# vv_mod_v1.net
KiCad netlist of a schematic drawn in EAGLE
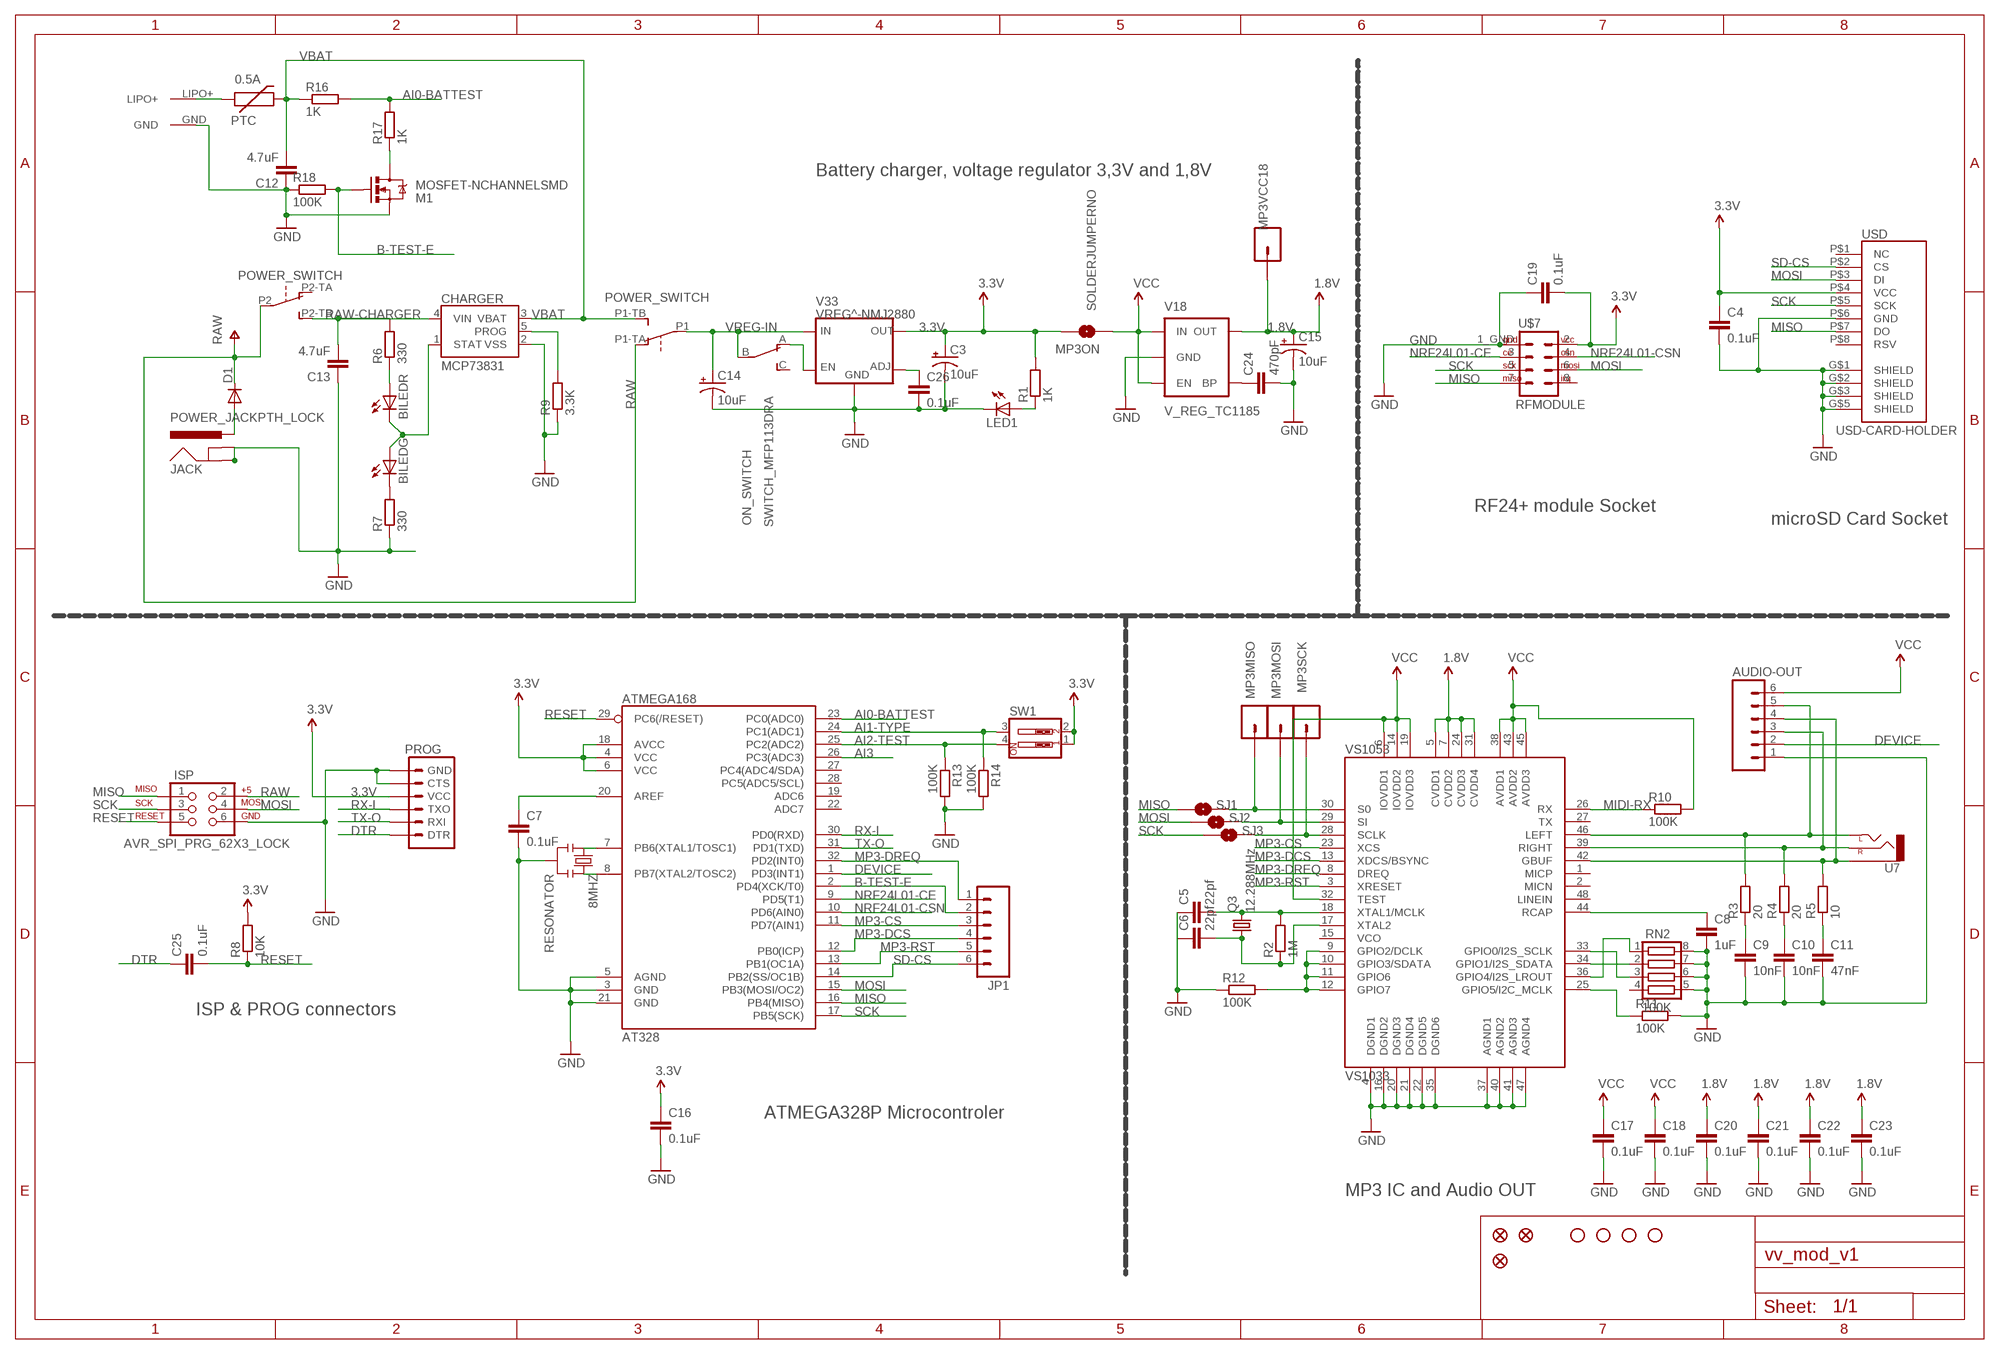
[diagram p0: schematic, sheet 1]

(export (version "E")
  (design (tool "Eeschema 10.0.6"))
  (components
    (comp (ref "0.5A")
      (value "PTC")
      (footprint "eagle-import:PTC-1210")
      (libsource (lib "eagle-import") (part "PTC"))
    )
    (comp (ref "8MHZ")
      (value "RESONATOR")
      (footprint "eagle-import:RESONATOR_7MM")
      (libsource (lib "eagle-import") (part "RESONATOR"))
    )
    (comp (ref "AT328")
      (value "ATMEGA168")
      (footprint "eagle-import:TQFP32-08")
      (libsource (lib "eagle-import") (part "ATMEGA168"))
    )
    (comp (ref "AUDIO-OUT")
      (value "M06LOCK")
      (footprint "eagle-import:1X06_LOCK")
      (libsource (lib "eagle-import") (part "M06LOCK"))
    )
    (comp (ref "BILED")
      (value "BILED")
      (footprint "eagle-import:2XLED")
      (libsource (lib "eagle-import") (part "BILED"))
    )
    (comp (ref "C3")
      (value "10uF")
      (footprint "eagle-import:EIA3216")
      (libsource (lib "eagle-import") (part "CAP_POL1206"))
    )
    (comp (ref "C4")
      (value "0.1uF")
      (footprint "eagle-import:C0805")
      (libsource (lib "eagle-import") (part "C-EUC0805"))
    )
    (comp (ref "C5")
      (value "22pf")
      (footprint "eagle-import:C0603")
      (libsource (lib "eagle-import") (part "C-EUC0603"))
    )
    (comp (ref "C6")
      (value "22pf")
      (footprint "eagle-import:C0603")
      (libsource (lib "eagle-import") (part "C-EUC0603"))
    )
    (comp (ref "C7")
      (value "0.1uF")
      (footprint "eagle-import:C0805")
      (libsource (lib "eagle-import") (part "C-EUC0805"))
    )
    (comp (ref "C8")
      (value "1uF")
      (footprint "eagle-import:C0603")
      (libsource (lib "eagle-import") (part "C-EUC0603"))
    )
    (comp (ref "C9")
      (value "10nF")
      (footprint "eagle-import:C0603")
      (libsource (lib "eagle-import") (part "C-EUC0603"))
    )
    (comp (ref "C10")
      (value "10nF")
      (footprint "eagle-import:C0603")
      (libsource (lib "eagle-import") (part "C-EUC0603"))
    )
    (comp (ref "C11")
      (value "47nF")
      (footprint "eagle-import:C0603")
      (libsource (lib "eagle-import") (part "C-EUC0603"))
    )
    (comp (ref "C12")
      (value "4.7uF")
      (footprint "eagle-import:C0603")
      (libsource (lib "eagle-import") (part "C-EUC0603"))
    )
    (comp (ref "C13")
      (value "4.7uF")
      (footprint "eagle-import:C0603")
      (libsource (lib "eagle-import") (part "C-EUC0603"))
    )
    (comp (ref "C14")
      (value "10uF")
      (footprint "eagle-import:EIA3216")
      (libsource (lib "eagle-import") (part "CAP_POL1206"))
    )
    (comp (ref "C15")
      (value "10uF")
      (footprint "eagle-import:EIA3216")
      (libsource (lib "eagle-import") (part "CAP_POL1206"))
    )
    (comp (ref "C16")
      (value "0.1uF")
      (footprint "eagle-import:C0805")
      (libsource (lib "eagle-import") (part "C-EUC0805"))
    )
    (comp (ref "C17")
      (value "0.1uF")
      (footprint "eagle-import:C0805")
      (libsource (lib "eagle-import") (part "C-EUC0805"))
    )
    (comp (ref "C18")
      (value "0.1uF")
      (footprint "eagle-import:C0805")
      (libsource (lib "eagle-import") (part "C-EUC0805"))
    )
    (comp (ref "C19")
      (value "0.1uF")
      (footprint "eagle-import:C0805")
      (libsource (lib "eagle-import") (part "C-EUC0805"))
    )
    (comp (ref "C20")
      (value "0.1uF")
      (footprint "eagle-import:C0805")
      (libsource (lib "eagle-import") (part "C-EUC0805"))
    )
    (comp (ref "C21")
      (value "0.1uF")
      (footprint "eagle-import:C0805")
      (libsource (lib "eagle-import") (part "C-EUC0805"))
    )
    (comp (ref "C22")
      (value "0.1uF")
      (footprint "eagle-import:C0805")
      (libsource (lib "eagle-import") (part "C-EUC0805"))
    )
    (comp (ref "C23")
      (value "0.1uF")
      (footprint "eagle-import:C0805")
      (libsource (lib "eagle-import") (part "C-EUC0805"))
    )
    (comp (ref "C24")
      (value "470pF")
      (footprint "eagle-import:C0603")
      (libsource (lib "eagle-import") (part "C-EUC0603"))
    )
    (comp (ref "C25")
      (value "0.1uF")
      (footprint "eagle-import:C0805")
      (libsource (lib "eagle-import") (part "C-EUC0805"))
    )
    (comp (ref "C26")
      (value "0.1uF")
      (footprint "eagle-import:C0805")
      (libsource (lib "eagle-import") (part "C-EUC0805"))
    )
    (comp (ref "CHARGER")
      (value "MCP73831")
      (footprint "eagle-import:SOT23-5")
      (libsource (lib "eagle-import") (part "MCP73831"))
    )
    (comp (ref "D1")
      (value "DIODESMA-KIT")
      (footprint "eagle-import:SMA-DIODE-KIT")
      (libsource (lib "eagle-import") (part "DIODESMA-KIT"))
    )
    (comp (ref "ISP")
      (value "AVR_SPI_PRG_62X3_LOCK")
      (footprint "eagle-import:2X3_LOCK")
      (libsource (lib "eagle-import") (part "AVR_SPI_PRG_62X3_LOCK"))
    )
    (comp (ref "JACK")
      (value "POWER_JACKPTH_LOCK")
      (footprint "eagle-import:POWER_JACK_PTH_LOCK")
      (libsource (lib "eagle-import") (part "POWER_JACKPTH_LOCK"))
    )
    (comp (ref "JP1")
      (value "M06SIP")
      (footprint "eagle-import:1X06")
      (libsource (lib "eagle-import") (part "M06SIP"))
    )
    (comp (ref "JP2")
      (value "FIDUCIAL1X2.5")
      (footprint "eagle-import:FIDUCIAL-1X2.5")
      (libsource (lib "eagle-import") (part "FIDUCIAL1X2.5"))
    )
    (comp (ref "JP3")
      (value "FIDUCIAL1X2.5")
      (footprint "eagle-import:FIDUCIAL-1X2.5")
      (libsource (lib "eagle-import") (part "FIDUCIAL1X2.5"))
    )
    (comp (ref "JP4")
      (value "STAND-OFF")
      (footprint "eagle-import:STAND-OFF")
      (libsource (lib "eagle-import") (part "STAND-OFF"))
    )
    (comp (ref "JP5")
      (value "STAND-OFF")
      (footprint "eagle-import:STAND-OFF")
      (libsource (lib "eagle-import") (part "STAND-OFF"))
    )
    (comp (ref "JP6")
      (value "STAND-OFF")
      (footprint "eagle-import:STAND-OFF")
      (libsource (lib "eagle-import") (part "STAND-OFF"))
    )
    (comp (ref "JP7")
      (value "STAND-OFF")
      (footprint "eagle-import:STAND-OFF")
      (libsource (lib "eagle-import") (part "STAND-OFF"))
    )
    (comp (ref "JP8")
      (value "FIDUCIAL1X2.5")
      (footprint "eagle-import:FIDUCIAL-1X2.5")
      (libsource (lib "eagle-import") (part "FIDUCIAL1X2.5"))
    )
    (comp (ref "LED1")
      (value "LED1206")
      (footprint "eagle-import:LED-1206")
      (libsource (lib "eagle-import") (part "LED1206"))
    )
    (comp (ref "M1")
      (value "MOSFET-NCHANNELSMD")
      (footprint "eagle-import:SOT23-3")
      (libsource (lib "eagle-import") (part "MOSFET-NCHANNELSMD"))
    )
    (comp (ref "MP3MISO")
      (value "M01SMD-4.5X1.5")
      (footprint "eagle-import:PAD-1.5X4.5")
      (libsource (lib "eagle-import") (part "M01SMD-4.5X1.5"))
    )
    (comp (ref "MP3MOSI")
      (value "M01SMD-4.5X1.5")
      (footprint "eagle-import:PAD-1.5X4.5")
      (libsource (lib "eagle-import") (part "M01SMD-4.5X1.5"))
    )
    (comp (ref "MP3ON")
      (value "SOLDERJUMPERNO")
      (footprint "eagle-import:SJ_2S-NO")
      (libsource (lib "eagle-import") (part "SOLDERJUMPERNO"))
    )
    (comp (ref "MP3SCK")
      (value "M01SMD-4.5X1.5")
      (footprint "eagle-import:PAD-1.5X4.5")
      (libsource (lib "eagle-import") (part "M01SMD-4.5X1.5"))
    )
    (comp (ref "MP3VCC18")
      (value "M01SMD-4.5X1.5")
      (footprint "eagle-import:PAD-1.5X4.5")
      (libsource (lib "eagle-import") (part "M01SMD-4.5X1.5"))
    )
    (comp (ref "ON_SWITCH")
      (value "SWITCH_MFP113DRA")
      (footprint "eagle-import:SWITCH")
      (libsource (lib "eagle-import") (part "SWITCH_MFP113DRA"))
    )
    (comp (ref "POWER_SWITCH")
      (value "JS202011SCQNPIN")
      (footprint "eagle-import:SWITCHPOWER")
      (libsource (lib "eagle-import") (part "JS202011SCQNPIN"))
    )
    (comp (ref "PROG")
      (value "ARDUINO_SERIAL_PROGRAMLOCK")
      (footprint "eagle-import:1X06_LOCK")
      (libsource (lib "eagle-import") (part "ARDUINO_SERIAL_PROGRAMLOCK"))
    )
    (comp (ref "Q3")
      (value "12.288MHz")
      (footprint "eagle-import:HC49UP")
      (libsource (lib "eagle-import") (part "CRYSTALHC49UP"))
    )
    (comp (ref "R1")
      (value "1K")
      (footprint "eagle-import:R0603")
      (libsource (lib "eagle-import") (part "R-EU_R0603"))
    )
    (comp (ref "R2")
      (value "1M")
      (footprint "eagle-import:R0603")
      (libsource (lib "eagle-import") (part "R-EU_R0603"))
    )
    (comp (ref "R3")
      (value "20")
      (footprint "eagle-import:R0603")
      (libsource (lib "eagle-import") (part "R-EU_R0603"))
    )
    (comp (ref "R4")
      (value "20")
      (footprint "eagle-import:R0603")
      (libsource (lib "eagle-import") (part "R-EU_R0603"))
    )
    (comp (ref "R5")
      (value "10")
      (footprint "eagle-import:R0603")
      (libsource (lib "eagle-import") (part "R-EU_R0603"))
    )
    (comp (ref "R6")
      (value "330")
      (footprint "eagle-import:R0805")
      (libsource (lib "eagle-import") (part "R-EU_R0805"))
    )
    (comp (ref "R7")
      (value "330")
      (footprint "eagle-import:R0805")
      (libsource (lib "eagle-import") (part "R-EU_R0805"))
    )
    (comp (ref "R8")
      (value "10K")
      (footprint "eagle-import:R0603")
      (libsource (lib "eagle-import") (part "R-EU_R0603"))
    )
    (comp (ref "R9")
      (value "3.3K")
      (footprint "eagle-import:R0603")
      (libsource (lib "eagle-import") (part "R-EU_R0603"))
    )
    (comp (ref "R10")
      (value "100K")
      (footprint "eagle-import:R0805")
      (libsource (lib "eagle-import") (part "R-EU_R0805"))
    )
    (comp (ref "R11")
      (value "100K")
      (footprint "eagle-import:R0805")
      (libsource (lib "eagle-import") (part "R-EU_R0805"))
    )
    (comp (ref "R12")
      (value "100K")
      (footprint "eagle-import:R0805")
      (libsource (lib "eagle-import") (part "R-EU_R0805"))
    )
    (comp (ref "R13")
      (value "100K")
      (footprint "eagle-import:R0805")
      (libsource (lib "eagle-import") (part "R-EU_R0805"))
    )
    (comp (ref "R14")
      (value "100K")
      (footprint "eagle-import:R0805")
      (libsource (lib "eagle-import") (part "R-EU_R0805"))
    )
    (comp (ref "R16")
      (value "1K")
      (footprint "eagle-import:R0603")
      (libsource (lib "eagle-import") (part "R-EU_R0603"))
    )
    (comp (ref "R17")
      (value "1K")
      (footprint "eagle-import:R0603")
      (libsource (lib "eagle-import") (part "R-EU_R0603"))
    )
    (comp (ref "R18")
      (value "100K")
      (footprint "eagle-import:R0805")
      (libsource (lib "eagle-import") (part "R-EU_R0805"))
    )
    (comp (ref "RN2")
      (value "100K")
      (footprint "eagle-import:CTS742C083")
      (libsource (lib "eagle-import") (part "CTS742C083"))
    )
    (comp (ref "SJ1")
      (value "SOLDERJUMPERNO")
      (footprint "eagle-import:SJ_2S-NO")
      (libsource (lib "eagle-import") (part "SOLDERJUMPERNO"))
    )
    (comp (ref "SJ2")
      (value "SOLDERJUMPERNO")
      (footprint "eagle-import:SJ_2S-NO")
      (libsource (lib "eagle-import") (part "SOLDERJUMPERNO"))
    )
    (comp (ref "SJ3")
      (value "SOLDERJUMPERNO")
      (footprint "eagle-import:SJ_2S-NO")
      (libsource (lib "eagle-import") (part "SOLDERJUMPERNO"))
    )
    (comp (ref "SW1")
      (value "SW_DIP-2")
      (footprint "eagle-import:DIPSWITCH-02")
      (libsource (lib "eagle-import") (part "SW_DIP-2"))
    )
    (comp (ref "U$7")
      (value "RFMODULE")
      (footprint "eagle-import:2X5_RFMODULE")
      (libsource (lib "eagle-import") (part "RFMODULE"))
    )
    (comp (ref "U$8")
      (value "LIPO_PAD")
      (footprint "eagle-import:2X1_LIPO_PAD")
      (libsource (lib "eagle-import") (part "LIPO_PAD"))
    )
    (comp (ref "U7")
      (value "AUDIO-JACKPTH")
      (footprint "eagle-import:AUDIO-JACK")
      (libsource (lib "eagle-import") (part "AUDIO-JACKPTH"))
    )
    (comp (ref "USD")
      (value "USD-CARD-HOLDER")
      (footprint "eagle-import:MICRO-SD-MOLEX-47579-001")
      (libsource (lib "eagle-import") (part "USD-CARD-HOLDER"))
    )
    (comp (ref "V18")
      (value "V_REG_TC1185")
      (footprint "eagle-import:SOT23-5")
      (libsource (lib "eagle-import") (part "V_REG_LDOSMD"))
    )
    (comp (ref "V33")
      (value "VREG^-NMJ2880")
      (footprint "eagle-import:SOT-89")
      (libsource (lib "eagle-import") (part "VREG^-NMJ2880"))
    )
    (comp (ref "VS1053")
      (value "VS1033")
      (footprint "eagle-import:LQFP-48")
      (libsource (lib "eagle-import") (part "VS1033"))
    )
  )
  (nets
    (net (code "1") (name "/AI0-BATTEST") (class "Default")
      (node (ref "AT328") (pin "23") (pinfunction "PC0(ADC0)_23") (pintype "bidirectional"))
      (node (ref "R16") (pin "2") (pinfunction "2_2") (pintype "passive"))
      (node (ref "R17") (pin "2") (pinfunction "2_2") (pintype "passive"))
    )
    (net (code "2") (name "/AI1-TYPE") (class "Default")
      (node (ref "AT328") (pin "24") (pinfunction "PC1(ADC1)_24") (pintype "bidirectional"))
      (node (ref "R14") (pin "1") (pinfunction "1_1") (pintype "passive"))
      (node (ref "SW1") (pin "3") (pinfunction "3_3") (pintype "passive"))
    )
    (net (code "3") (name "/AI2-TEST") (class "Default")
      (node (ref "AT328") (pin "25") (pinfunction "PC2(ADC2)_25") (pintype "bidirectional"))
      (node (ref "R13") (pin "1") (pinfunction "1_1") (pintype "passive"))
      (node (ref "SW1") (pin "4") (pinfunction "4_4") (pintype "passive"))
    )
    (net (code "4") (name "/AI3") (class "Default")
      (node (ref "AT328") (pin "26") (pinfunction "PC3(ADC3)_26") (pintype "bidirectional"))
    )
    (net (code "5") (name "/B-TEST-E") (class "Default")
      (node (ref "AT328") (pin "2") (pinfunction "PD4(XCK/T0)_2") (pintype "bidirectional"))
      (node (ref "JP1") (pin "2") (pinfunction "2_2") (pintype "passive"))
      (node (ref "M1") (pin "1") (pinfunction "G_1") (pintype "passive"))
      (node (ref "R18") (pin "2") (pinfunction "2_2") (pintype "passive"))
    )
    (net (code "6") (name "/DEVICE") (class "Default")
      (node (ref "AT328") (pin "1") (pinfunction "PD3(INT1)_1") (pintype "bidirectional"))
      (node (ref "AUDIO-OUT") (pin "2") (pinfunction "2_2") (pintype "passive"))
    )
    (net (code "7") (name "/DTR") (class "Default")
      (node (ref "C25") (pin "1") (pinfunction "1_1") (pintype "passive"))
      (node (ref "PROG") (pin "1") (pinfunction "DTR_1") (pintype "passive"))
    )
    (net (code "8") (name "/MIDI-RX") (class "Default")
      (node (ref "R10") (pin "1") (pinfunction "1_1") (pintype "passive"))
      (node (ref "VS1053") (pin "26") (pinfunction "RX_26") (pintype "bidirectional"))
    )
    (net (code "9") (name "/MISO") (class "Default")
      (node (ref "AT328") (pin "16") (pinfunction "PB4(MISO)_16") (pintype "bidirectional"))
      (node (ref "ISP") (pin "1") (pinfunction "1_1") (pintype "passive"))
      (node (ref "SJ1") (pin "1") (pinfunction "1_1") (pintype "passive"))
      (node (ref "U$7") (pin "7") (pinfunction "MISO_7") (pintype "passive"))
      (node (ref "USD") (pin "P$7") (pinfunction "DO_P$7") (pintype "bidirectional"))
    )
    (net (code "10") (name "/MOSI") (class "Default")
      (node (ref "AT328") (pin "15") (pinfunction "PB3(MOSI/OC2)_15") (pintype "bidirectional"))
      (node (ref "ISP") (pin "4") (pinfunction "4_4") (pintype "passive"))
      (node (ref "SJ2") (pin "1") (pinfunction "1_1") (pintype "passive"))
      (node (ref "U$7") (pin "6") (pinfunction "MOSI_6") (pintype "passive"))
      (node (ref "USD") (pin "P$3") (pinfunction "DI_P$3") (pintype "bidirectional"))
    )
    (net (code "11") (name "/MP3-CS") (class "Default")
      (node (ref "AT328") (pin "11") (pinfunction "PD7(AIN1)_11") (pintype "bidirectional"))
      (node (ref "JP1") (pin "3") (pinfunction "3_3") (pintype "passive"))
      (node (ref "VS1053") (pin "23") (pinfunction "XCS_23") (pintype "bidirectional"))
    )
    (net (code "12") (name "/MP3-DCS") (class "Default")
      (node (ref "AT328") (pin "12") (pinfunction "PB0(ICP)_12") (pintype "bidirectional"))
      (node (ref "JP1") (pin "4") (pinfunction "4_4") (pintype "passive"))
      (node (ref "VS1053") (pin "13") (pinfunction "XDCS/BSYNC_13") (pintype "bidirectional"))
    )
    (net (code "13") (name "/MP3-DREQ") (class "Default")
      (node (ref "AT328") (pin "32") (pinfunction "PD2(INT0)_32") (pintype "bidirectional"))
      (node (ref "JP1") (pin "1") (pinfunction "1_1") (pintype "passive"))
      (node (ref "VS1053") (pin "8") (pinfunction "DREQ_8") (pintype "bidirectional"))
    )
    (net (code "14") (name "/MP3-RST") (class "Default")
      (node (ref "AT328") (pin "13") (pinfunction "PB1(OC1A)_13") (pintype "bidirectional"))
      (node (ref "JP1") (pin "5") (pinfunction "5_5") (pintype "passive"))
      (node (ref "VS1053") (pin "3") (pinfunction "XRESET_3") (pintype "bidirectional"))
    )
    (net (code "15") (name "/NRF24L01-CE") (class "Default")
      (node (ref "AT328") (pin "9") (pinfunction "PD5(T1)_9") (pintype "bidirectional"))
      (node (ref "U$7") (pin "3") (pinfunction "CE_3") (pintype "passive"))
    )
    (net (code "16") (name "/NRF24L01-CSN") (class "Default")
      (node (ref "AT328") (pin "10") (pinfunction "PD6(AIN0)_10") (pintype "bidirectional"))
      (node (ref "U$7") (pin "4") (pinfunction "CSN_4") (pintype "passive"))
    )
    (net (code "17") (name "/RAW-CHARGER") (class "Default")
      (node (ref "C13") (pin "2") (pinfunction "2_2") (pintype "passive"))
      (node (ref "CHARGER") (pin "4") (pinfunction "VIN_4") (pintype "power_in"))
      (node (ref "POWER_SWITCH") (pin "P2-TB") (pinfunction "S_P2-TB") (pintype "passive"))
      (node (ref "R6") (pin "2") (pinfunction "2_2") (pintype "passive"))
    )
    (net (code "18") (name "/RESET") (class "Default")
      (node (ref "AT328") (pin "29") (pinfunction "PC6(/RESET)_29") (pintype "bidirectional"))
      (node (ref "C25") (pin "2") (pinfunction "2_2") (pintype "passive"))
      (node (ref "ISP") (pin "5") (pinfunction "5_5") (pintype "passive"))
      (node (ref "R8") (pin "1") (pinfunction "1_1") (pintype "passive"))
    )
    (net (code "19") (name "/RX-I") (class "Default")
      (node (ref "AT328") (pin "30") (pinfunction "PD0(RXD)_30") (pintype "bidirectional"))
      (node (ref "PROG") (pin "3") (pinfunction "TXO_3") (pintype "passive"))
    )
    (net (code "20") (name "/SCK") (class "Default")
      (node (ref "AT328") (pin "17") (pinfunction "PB5(SCK)_17") (pintype "bidirectional"))
      (node (ref "ISP") (pin "3") (pinfunction "3_3") (pintype "passive"))
      (node (ref "SJ3") (pin "1") (pinfunction "1_1") (pintype "passive"))
      (node (ref "U$7") (pin "5") (pinfunction "SCK_5") (pintype "passive"))
      (node (ref "USD") (pin "P$5") (pinfunction "SCK_P$5") (pintype "bidirectional"))
    )
    (net (code "21") (name "/SD-CS") (class "Default")
      (node (ref "AT328") (pin "14") (pinfunction "PB2(SS/OC1B)_14") (pintype "bidirectional"))
      (node (ref "JP1") (pin "6") (pinfunction "6_6") (pintype "passive"))
      (node (ref "USD") (pin "P$2") (pinfunction "CS_P$2") (pintype "bidirectional"))
    )
    (net (code "22") (name "/TX-O") (class "Default")
      (node (ref "AT328") (pin "31") (pinfunction "PD1(TXD)_31") (pintype "bidirectional"))
      (node (ref "PROG") (pin "2") (pinfunction "RXI_2") (pintype "passive"))
    )
    (net (code "23") (name "/VBAT") (class "Default")
      (node (ref "0.5A") (pin "2") (pinfunction "2_2") (pintype "bidirectional"))
      (node (ref "C12") (pin "2") (pinfunction "2_2") (pintype "passive"))
      (node (ref "CHARGER") (pin "3") (pinfunction "VBAT_3") (pintype "power_in"))
      (node (ref "POWER_SWITCH") (pin "P1-TB") (pinfunction "S_P1-TB") (pintype "passive"))
      (node (ref "R16") (pin "1") (pinfunction "1_1") (pintype "passive"))
    )
    (net (code "24") (name "/VREG-IN") (class "Default")
      (node (ref "C14") (pin "A") (pinfunction "+_A") (pintype "passive"))
      (node (ref "ON_SWITCH") (pin "B") (pinfunction "P_B") (pintype "passive"))
      (node (ref "POWER_SWITCH") (pin "P1") (pinfunction "P_P1") (pintype "passive"))
      (node (ref "V33") (pin "5") (pinfunction "IN_5") (pintype "input"))
    )
    (net (code "25") (name "1.8V") (class "Default")
      (node (ref "C15") (pin "A") (pinfunction "+_A") (pintype "passive"))
      (node (ref "C20") (pin "1") (pinfunction "1_1") (pintype "passive"))
      (node (ref "C21") (pin "1") (pinfunction "1_1") (pintype "passive"))
      (node (ref "C22") (pin "1") (pinfunction "1_1") (pintype "passive"))
      (node (ref "C23") (pin "1") (pinfunction "1_1") (pintype "passive"))
      (node (ref "MP3VCC18") (pin "P$1") (pinfunction "1_P$1") (pintype "passive"))
      (node (ref "V18") (pin "5") (pinfunction "OUT_5") (pintype "passive"))
      (node (ref "VS1053") (pin "24") (pinfunction "CVDD3_24") (pintype "bidirectional"))
      (node (ref "VS1053") (pin "31") (pinfunction "CVDD4_31") (pintype "bidirectional"))
      (node (ref "VS1053") (pin "5") (pinfunction "CVDD1_5") (pintype "bidirectional"))
      (node (ref "VS1053") (pin "7") (pinfunction "CVDD2_7") (pintype "bidirectional"))
    )
    (net (code "26") (name "3.3V") (class "Default")
      (node (ref "AT328") (pin "18") (pinfunction "AVCC_18") (pintype "bidirectional"))
      (node (ref "AT328") (pin "4") (pinfunction "VCC_4") (pintype "bidirectional"))
      (node (ref "AT328") (pin "6") (pinfunction "VCC_6") (pintype "bidirectional"))
      (node (ref "C16") (pin "1") (pinfunction "1_1") (pintype "passive"))
      (node (ref "C19") (pin "2") (pinfunction "2_2") (pintype "passive"))
      (node (ref "C3") (pin "A") (pinfunction "+_A") (pintype "passive"))
      (node (ref "C4") (pin "1") (pinfunction "1_1") (pintype "passive"))
      (node (ref "MP3ON") (pin "2") (pinfunction "2_2") (pintype "passive"))
      (node (ref "PROG") (pin "4") (pinfunction "VCC_4") (pintype "passive"))
      (node (ref "R1") (pin "2") (pinfunction "2_2") (pintype "passive"))
      (node (ref "R8") (pin "2") (pinfunction "2_2") (pintype "passive"))
      (node (ref "SW1") (pin "1") (pinfunction "1_1") (pintype "passive"))
      (node (ref "SW1") (pin "2") (pinfunction "2_2") (pintype "passive"))
      (node (ref "U$7") (pin "2") (pinfunction "VCC_2") (pintype "passive"))
      (node (ref "USD") (pin "P$4") (pinfunction "VCC_P$4") (pintype "bidirectional"))
      (node (ref "V33") (pin "4") (pinfunction "OUT_4") (pintype "output"))
    )
    (net (code "27") (name "GND") (class "Default")
      (node (ref "8MHZ") (pin "2") (pinfunction "2_2") (pintype "passive"))
      (node (ref "AT328") (pin "21") (pinfunction "GND_21") (pintype "bidirectional"))
      (node (ref "AT328") (pin "3") (pinfunction "GND_3") (pintype "bidirectional"))
      (node (ref "AT328") (pin "5") (pinfunction "AGND_5") (pintype "bidirectional"))
      (node (ref "AUDIO-OUT") (pin "1") (pinfunction "1_1") (pintype "passive"))
      (node (ref "C10") (pin "2") (pinfunction "2_2") (pintype "passive"))
      (node (ref "C11") (pin "2") (pinfunction "2_2") (pintype "passive"))
      (node (ref "C12") (pin "1") (pinfunction "1_1") (pintype "passive"))
      (node (ref "C13") (pin "1") (pinfunction "1_1") (pintype "passive"))
      (node (ref "C14") (pin "C") (pinfunction "-_C") (pintype "passive"))
      (node (ref "C15") (pin "C") (pinfunction "-_C") (pintype "passive"))
      (node (ref "C16") (pin "2") (pinfunction "2_2") (pintype "passive"))
      (node (ref "C17") (pin "2") (pinfunction "2_2") (pintype "passive"))
      (node (ref "C18") (pin "2") (pinfunction "2_2") (pintype "passive"))
      (node (ref "C19") (pin "1") (pinfunction "1_1") (pintype "passive"))
      (node (ref "C20") (pin "2") (pinfunction "2_2") (pintype "passive"))
      (node (ref "C21") (pin "2") (pinfunction "2_2") (pintype "passive"))
      (node (ref "C22") (pin "2") (pinfunction "2_2") (pintype "passive"))
      (node (ref "C23") (pin "2") (pinfunction "2_2") (pintype "passive"))
      (node (ref "C24") (pin "2") (pinfunction "2_2") (pintype "passive"))
      (node (ref "C26") (pin "2") (pinfunction "2_2") (pintype "passive"))
      (node (ref "C3") (pin "C") (pinfunction "-_C") (pintype "passive"))
      (node (ref "C4") (pin "2") (pinfunction "2_2") (pintype "passive"))
      (node (ref "C5") (pin "1") (pinfunction "1_1") (pintype "passive"))
      (node (ref "C6") (pin "1") (pinfunction "1_1") (pintype "passive"))
      (node (ref "C7") (pin "2") (pinfunction "2_2") (pintype "passive"))
      (node (ref "C8") (pin "2") (pinfunction "2_2") (pintype "passive"))
      (node (ref "C9") (pin "2") (pinfunction "2_2") (pintype "passive"))
      (node (ref "CHARGER") (pin "2") (pinfunction "VSS_2") (pintype "power_in"))
      (node (ref "ISP") (pin "6") (pinfunction "6_6") (pintype "passive"))
      (node (ref "JACK") (pin "GND") (pinfunction "GND_GND") (pintype "bidirectional"))
      (node (ref "JACK") (pin "GNDBREAK") (pinfunction "GNDBREAK_GNDBREAK") (pintype "bidirectional"))
      (node (ref "LED1") (pin "C") (pinfunction "C_C") (pintype "passive"))
      (node (ref "M1") (pin "2") (pinfunction "S_2") (pintype "passive"))
      (node (ref "PROG") (pin "5") (pinfunction "CTS_5") (pintype "passive"))
      (node (ref "PROG") (pin "6") (pinfunction "GND_6") (pintype "passive"))
      (node (ref "R11") (pin "2") (pinfunction "2_2") (pintype "passive"))
      (node (ref "R12") (pin "1") (pinfunction "1_1") (pintype "passive"))
      (node (ref "R13") (pin "2") (pinfunction "2_2") (pintype "passive"))
      (node (ref "R14") (pin "2") (pinfunction "2_2") (pintype "passive"))
      (node (ref "R18") (pin "1") (pinfunction "1_1") (pintype "passive"))
      (node (ref "R7") (pin "1") (pinfunction "1_1") (pintype "passive"))
      (node (ref "R9") (pin "1") (pinfunction "1_1") (pintype "passive"))
      (node (ref "RN2") (pin "5") (pinfunction "5_5") (pintype "passive"))
      (node (ref "RN2") (pin "6") (pinfunction "6_6") (pintype "passive"))
      (node (ref "RN2") (pin "7") (pinfunction "7_7") (pintype "passive"))
      (node (ref "RN2") (pin "8") (pinfunction "8_8") (pintype "passive"))
      (node (ref "U$7") (pin "1_GND") (pinfunction "GND_1_GND") (pintype "passive"))
      (node (ref "U$8") (pin "GND") (pinfunction "GND_GND") (pintype "bidirectional"))
      (node (ref "USD") (pin "G$1") (pinfunction "SHIELD_G$1") (pintype "bidirectional"))
      (node (ref "USD") (pin "G$2") (pinfunction "SHIELD_G$2") (pintype "bidirectional"))
      (node (ref "USD") (pin "G$3") (pinfunction "SHIELD_G$3") (pintype "bidirectional"))
      (node (ref "USD") (pin "G$5") (pinfunction "SHIELD_G$5") (pintype "bidirectional"))
      (node (ref "USD") (pin "P$6") (pinfunction "GND_P$6") (pintype "bidirectional"))
      (node (ref "V18") (pin "2") (pinfunction "GND_2") (pintype "input"))
      (node (ref "V33") (pin "2") (pinfunction "GND_2") (pintype "bidirectional"))
      (node (ref "VS1053") (pin "16") (pinfunction "DGND2_16") (pintype "bidirectional"))
      (node (ref "VS1053") (pin "20") (pinfunction "DGND3_20") (pintype "bidirectional"))
      (node (ref "VS1053") (pin "21") (pinfunction "DGND4_21") (pintype "bidirectional"))
      (node (ref "VS1053") (pin "22") (pinfunction "DGND5_22") (pintype "bidirectional"))
      (node (ref "VS1053") (pin "35") (pinfunction "DGND6_35") (pintype "bidirectional"))
      (node (ref "VS1053") (pin "37") (pinfunction "AGND1_37") (pintype "bidirectional"))
      (node (ref "VS1053") (pin "4") (pinfunction "DGND1_4") (pintype "bidirectional"))
      (node (ref "VS1053") (pin "40") (pinfunction "AGND2_40") (pintype "bidirectional"))
      (node (ref "VS1053") (pin "41") (pinfunction "AGND3_41") (pintype "bidirectional"))
      (node (ref "VS1053") (pin "47") (pinfunction "AGND4_47") (pintype "bidirectional"))
    )
    (net (code "28") (name "Net-(0.5A-Pad1)") (class "Default")
      (node (ref "0.5A") (pin "1") (pinfunction "1_1") (pintype "bidirectional"))
      (node (ref "U$8") (pin "LIPO+") (pinfunction "LIPO+_LIPO+") (pintype "bidirectional"))
    )
    (net (code "29") (name "Net-(AT328-AREF)") (class "Default")
      (node (ref "AT328") (pin "20") (pinfunction "AREF_20") (pintype "bidirectional"))
      (node (ref "C7") (pin "1") (pinfunction "1_1") (pintype "passive"))
    )
    (net (code "30") (name "Net-(AT328-PB6(XTAL1{slash}TOSC1))") (class "Default")
      (node (ref "8MHZ") (pin "1") (pinfunction "1_1") (pintype "passive"))
      (node (ref "AT328") (pin "7") (pinfunction "PB6(XTAL1/TOSC1)_7") (pintype "bidirectional"))
    )
    (net (code "31") (name "Net-(AT328-PB7(XTAL2{slash}TOSC2))") (class "Default")
      (node (ref "8MHZ") (pin "3") (pinfunction "3_3") (pintype "passive"))
      (node (ref "AT328") (pin "8") (pinfunction "PB7(XTAL2/TOSC2)_8") (pintype "bidirectional"))
    )
    (net (code "32") (name "Net-(BILEDA-A)") (class "Default")
      (node (ref "BILED") (pin "A1") (pinfunction "A_A1") (pintype "passive"))
      (node (ref "BILED") (pin "C4") (pinfunction "C_C4") (pintype "passive"))
      (node (ref "CHARGER") (pin "1") (pinfunction "STAT_1") (pintype "output"))
    )
    (net (code "33") (name "Net-(BILEDA-C)") (class "Default")
      (node (ref "BILED") (pin "C3") (pinfunction "C_C3") (pintype "passive"))
      (node (ref "R7") (pin "2") (pinfunction "2_2") (pintype "passive"))
    )
    (net (code "34") (name "Net-(BILEDB-A)") (class "Default")
      (node (ref "BILED") (pin "A2") (pinfunction "A_A2") (pintype "passive"))
      (node (ref "R6") (pin "1") (pinfunction "1_1") (pintype "passive"))
    )
    (net (code "35") (name "Net-(C9-Pad1)") (class "Default")
      (node (ref "C9") (pin "1") (pinfunction "1_1") (pintype "passive"))
      (node (ref "R3") (pin "1") (pinfunction "1_1") (pintype "passive"))
    )
    (net (code "36") (name "Net-(C10-Pad1)") (class "Default")
      (node (ref "C10") (pin "1") (pinfunction "1_1") (pintype "passive"))
      (node (ref "R4") (pin "1") (pinfunction "1_1") (pintype "passive"))
    )
    (net (code "37") (name "Net-(C11-Pad1)") (class "Default")
      (node (ref "C11") (pin "1") (pinfunction "1_1") (pintype "passive"))
      (node (ref "R5") (pin "1") (pinfunction "1_1") (pintype "passive"))
    )
    (net (code "38") (name "Net-(CHARGER-PROG)") (class "Default")
      (node (ref "CHARGER") (pin "5") (pinfunction "PROG_5") (pintype "input"))
      (node (ref "R9") (pin "2") (pinfunction "2_2") (pintype "passive"))
    )
    (net (code "39") (name "Net-(D1-PadA)") (class "Default")
      (node (ref "D1") (pin "A") (pinfunction "A_A") (pintype "passive"))
      (node (ref "JACK") (pin "PWR") (pinfunction "PWR_PWR") (pintype "bidirectional"))
    )
    (net (code "40") (name "Net-(LED1-PadA)") (class "Default")
      (node (ref "LED1") (pin "A") (pinfunction "A_A") (pintype "passive"))
      (node (ref "R1") (pin "1") (pinfunction "1_1") (pintype "passive"))
    )
    (net (code "41") (name "Net-(M1-D)") (class "Default")
      (node (ref "M1") (pin "3") (pinfunction "D_3") (pintype "passive"))
      (node (ref "R17") (pin "1") (pinfunction "1_1") (pintype "passive"))
    )
    (net (code "42") (name "Net-(MP3MISO-1)") (class "Default")
      (node (ref "MP3MISO") (pin "P$1") (pinfunction "1_P$1") (pintype "passive"))
      (node (ref "SJ1") (pin "2") (pinfunction "2_2") (pintype "passive"))
      (node (ref "VS1053") (pin "30") (pinfunction "S0_30") (pintype "bidirectional"))
    )
    (net (code "43") (name "Net-(MP3MOSI-1)") (class "Default")
      (node (ref "MP3MOSI") (pin "P$1") (pinfunction "1_P$1") (pintype "passive"))
      (node (ref "SJ2") (pin "2") (pinfunction "2_2") (pintype "passive"))
      (node (ref "VS1053") (pin "29") (pinfunction "SI_29") (pintype "bidirectional"))
    )
    (net (code "44") (name "Net-(MP3SCK-1)") (class "Default")
      (node (ref "MP3SCK") (pin "P$1") (pinfunction "1_P$1") (pintype "passive"))
      (node (ref "SJ3") (pin "2") (pinfunction "2_2") (pintype "passive"))
      (node (ref "VS1053") (pin "28") (pinfunction "SCLK_28") (pintype "bidirectional"))
    )
    (net (code "45") (name "Net-(ON_SWITCH-O)") (class "Default")
      (node (ref "ON_SWITCH") (pin "A") (pinfunction "O_A") (pintype "passive"))
      (node (ref "V33") (pin "1") (pinfunction "EN_1") (pintype "bidirectional"))
    )
    (net (code "46") (name "Net-(U7-LEFT)") (class "Default")
      (node (ref "AUDIO-OUT") (pin "5") (pinfunction "5_5") (pintype "passive"))
      (node (ref "R3") (pin "2") (pinfunction "2_2") (pintype "passive"))
      (node (ref "U7") (pin "TIP") (pinfunction "LEFT_TIP") (pintype "bidirectional"))
      (node (ref "VS1053") (pin "46") (pinfunction "LEFT_46") (pintype "bidirectional"))
    )
    (net (code "47") (name "Net-(U7-RIGHT)") (class "Default")
      (node (ref "AUDIO-OUT") (pin "3") (pinfunction "3_3") (pintype "passive"))
      (node (ref "R4") (pin "2") (pinfunction "2_2") (pintype "passive"))
      (node (ref "U7") (pin "RING") (pinfunction "RIGHT_RING") (pintype "bidirectional"))
      (node (ref "VS1053") (pin "39") (pinfunction "RIGHT_39") (pintype "bidirectional"))
    )
    (net (code "48") (name "Net-(V18-BP)") (class "Default")
      (node (ref "C24") (pin "1") (pinfunction "1_1") (pintype "passive"))
      (node (ref "V18") (pin "4") (pinfunction "BP_4") (pintype "input"))
    )
    (net (code "49") (name "Net-(V33-ADJ)") (class "Default")
      (node (ref "C26") (pin "1") (pinfunction "1_1") (pintype "passive"))
      (node (ref "V33") (pin "3") (pinfunction "ADJ_3") (pintype "input"))
    )
    (net (code "50") (name "Net-(VS1053-GBUF)") (class "Default")
      (node (ref "AUDIO-OUT") (pin "4") (pinfunction "4_4") (pintype "passive"))
      (node (ref "R5") (pin "2") (pinfunction "2_2") (pintype "passive"))
      (node (ref "U7") (pin "SLEEVE") (pinfunction "SLEEVE_SLEEVE") (pintype "bidirectional"))
      (node (ref "VS1053") (pin "42") (pinfunction "GBUF_42") (pintype "bidirectional"))
    )
    (net (code "51") (name "Net-(VS1053-GPIO0{slash}I2S_SCLK)") (class "Default")
      (node (ref "RN2") (pin "3") (pinfunction "3_3") (pintype "passive"))
      (node (ref "VS1053") (pin "33") (pinfunction "GPIO0/I2S_SCLK_33") (pintype "bidirectional"))
    )
    (net (code "52") (name "Net-(VS1053-GPIO1{slash}I2S_SDATA)") (class "Default")
      (node (ref "RN2") (pin "2") (pinfunction "2_2") (pintype "passive"))
      (node (ref "VS1053") (pin "34") (pinfunction "GPIO1/I2S_SDATA_34") (pintype "bidirectional"))
    )
    (net (code "53") (name "Net-(VS1053-GPIO2{slash}DCLK)") (class "Default")
      (node (ref "R12") (pin "2") (pinfunction "2_2") (pintype "passive"))
      (node (ref "VS1053") (pin "10") (pinfunction "GPIO3/SDATA_10") (pintype "bidirectional"))
      (node (ref "VS1053") (pin "11") (pinfunction "GPIO6_11") (pintype "bidirectional"))
      (node (ref "VS1053") (pin "12") (pinfunction "GPIO7_12") (pintype "bidirectional"))
      (node (ref "VS1053") (pin "9") (pinfunction "GPIO2/DCLK_9") (pintype "bidirectional"))
    )
    (net (code "54") (name "Net-(VS1053-GPIO4{slash}I2S_LROUT)") (class "Default")
      (node (ref "RN2") (pin "1") (pinfunction "1_1") (pintype "passive"))
      (node (ref "VS1053") (pin "36") (pinfunction "GPIO4/I2S_LROUT_36") (pintype "bidirectional"))
    )
    (net (code "55") (name "Net-(VS1053-GPIO5{slash}I2C_MCLK)") (class "Default")
      (node (ref "R11") (pin "1") (pinfunction "1_1") (pintype "passive"))
      (node (ref "VS1053") (pin "25") (pinfunction "GPIO5/I2C_MCLK_25") (pintype "bidirectional"))
    )
    (net (code "56") (name "Net-(VS1053-RCAP)") (class "Default")
      (node (ref "C8") (pin "1") (pinfunction "1_1") (pintype "passive"))
      (node (ref "VS1053") (pin "44") (pinfunction "RCAP_44") (pintype "bidirectional"))
    )
    (net (code "57") (name "Net-(VS1053-XTAL1{slash}MCLK)") (class "Default")
      (node (ref "C5") (pin "2") (pinfunction "2_2") (pintype "passive"))
      (node (ref "Q3") (pin "2") (pinfunction "2_2") (pintype "passive"))
      (node (ref "R2") (pin "2") (pinfunction "2_2") (pintype "passive"))
      (node (ref "VS1053") (pin "18") (pinfunction "XTAL1/MCLK_18") (pintype "bidirectional"))
    )
    (net (code "58") (name "Net-(VS1053-XTAL2)") (class "Default")
      (node (ref "C6") (pin "2") (pinfunction "2_2") (pintype "passive"))
      (node (ref "Q3") (pin "1") (pinfunction "1_1") (pintype "passive"))
      (node (ref "R2") (pin "1") (pinfunction "1_1") (pintype "passive"))
      (node (ref "VS1053") (pin "17") (pinfunction "XTAL2_17") (pintype "bidirectional"))
    )
    (net (code "59") (name "RAW") (class "Default")
      (node (ref "D1") (pin "C") (pinfunction "C_C") (pintype "passive"))
      (node (ref "ISP") (pin "2") (pinfunction "2_2") (pintype "passive"))
      (node (ref "POWER_SWITCH") (pin "P1-TA") (pinfunction "O_P1-TA") (pintype "passive"))
      (node (ref "POWER_SWITCH") (pin "P2") (pinfunction "P_P2") (pintype "passive"))
    )
    (net (code "60") (name "VCC") (class "Default")
      (node (ref "AUDIO-OUT") (pin "6") (pinfunction "6_6") (pintype "passive"))
      (node (ref "C17") (pin "1") (pinfunction "1_1") (pintype "passive"))
      (node (ref "C18") (pin "1") (pinfunction "1_1") (pintype "passive"))
      (node (ref "MP3ON") (pin "1") (pinfunction "1_1") (pintype "passive"))
      (node (ref "R10") (pin "2") (pinfunction "2_2") (pintype "passive"))
      (node (ref "V18") (pin "1") (pinfunction "IN_1") (pintype "input"))
      (node (ref "V18") (pin "3") (pinfunction "EN_3") (pintype "input"))
      (node (ref "VS1053") (pin "14") (pinfunction "IOVDD2_14") (pintype "bidirectional"))
      (node (ref "VS1053") (pin "19") (pinfunction "IOVDD3_19") (pintype "bidirectional"))
      (node (ref "VS1053") (pin "32") (pinfunction "TEST_32") (pintype "bidirectional"))
      (node (ref "VS1053") (pin "38") (pinfunction "AVDD1_38") (pintype "bidirectional"))
      (node (ref "VS1053") (pin "43") (pinfunction "AVDD2_43") (pintype "bidirectional"))
      (node (ref "VS1053") (pin "45") (pinfunction "AVDD3_45") (pintype "bidirectional"))
      (node (ref "VS1053") (pin "6") (pinfunction "IOVDD1_6") (pintype "bidirectional"))
    )
    (net (code "61") (name "unconnected-(AT328-ADC6-Pad19)") (class "Default")
      (node (ref "AT328") (pin "19") (pinfunction "ADC6_19") (pintype "bidirectional"))
    )
    (net (code "62") (name "unconnected-(AT328-ADC7-Pad22)") (class "Default")
      (node (ref "AT328") (pin "22") (pinfunction "ADC7_22") (pintype "bidirectional"))
    )
    (net (code "63") (name "unconnected-(AT328-PC4(ADC4{slash}SDA)-Pad27)") (class "Default")
      (node (ref "AT328") (pin "27") (pinfunction "PC4(ADC4/SDA)_27") (pintype "bidirectional"))
    )
    (net (code "64") (name "unconnected-(AT328-PC5(ADC5{slash}SCL)-Pad28)") (class "Default")
      (node (ref "AT328") (pin "28") (pinfunction "PC5(ADC5/SCL)_28") (pintype "bidirectional"))
    )
    (net (code "65") (name "unconnected-(ON_SWITCH-S-PadC)") (class "Default")
      (node (ref "ON_SWITCH") (pin "C") (pinfunction "S_C") (pintype "passive"))
    )
    (net (code "66") (name "unconnected-(POWER_SWITCHB-O-PadP2-TA)") (class "Default")
      (node (ref "POWER_SWITCH") (pin "P2-TA") (pinfunction "O_P2-TA") (pintype "passive"))
    )
    (net (code "67") (name "unconnected-(RN2-Pad4)") (class "Default")
      (node (ref "RN2") (pin "4") (pinfunction "4_4") (pintype "passive"))
    )
    (net (code "68") (name "unconnected-(U$7-IRQ-Pad8)") (class "Default")
      (node (ref "U$7") (pin "8") (pinfunction "IRQ_8") (pintype "passive"))
    )
    (net (code "69") (name "unconnected-(USD-NC-PadP$1)") (class "Default")
      (node (ref "USD") (pin "P$1") (pinfunction "NC_P$1") (pintype "bidirectional"))
    )
    (net (code "70") (name "unconnected-(USD-RSV-PadP$8)") (class "Default")
      (node (ref "USD") (pin "P$8") (pinfunction "RSV_P$8") (pintype "bidirectional"))
    )
    (net (code "71") (name "unconnected-(VS1053-LINEIN-Pad48)") (class "Default")
      (node (ref "VS1053") (pin "48") (pinfunction "LINEIN_48") (pintype "bidirectional"))
    )
    (net (code "72") (name "unconnected-(VS1053-MICN-Pad2)") (class "Default")
      (node (ref "VS1053") (pin "2") (pinfunction "MICN_2") (pintype "bidirectional"))
    )
    (net (code "73") (name "unconnected-(VS1053-MICP-Pad1)") (class "Default")
      (node (ref "VS1053") (pin "1") (pinfunction "MICP_1") (pintype "bidirectional"))
    )
    (net (code "74") (name "unconnected-(VS1053-TX-Pad27)") (class "Default")
      (node (ref "VS1053") (pin "27") (pinfunction "TX_27") (pintype "bidirectional"))
    )
    (net (code "75") (name "unconnected-(VS1053-VCO-Pad15)") (class "Default")
      (node (ref "VS1053") (pin "15") (pinfunction "VCO_15") (pintype "bidirectional"))
    )
  )
)
